# User_Interface.net
KiCad netlist of a schematic drawn in Altium Designer
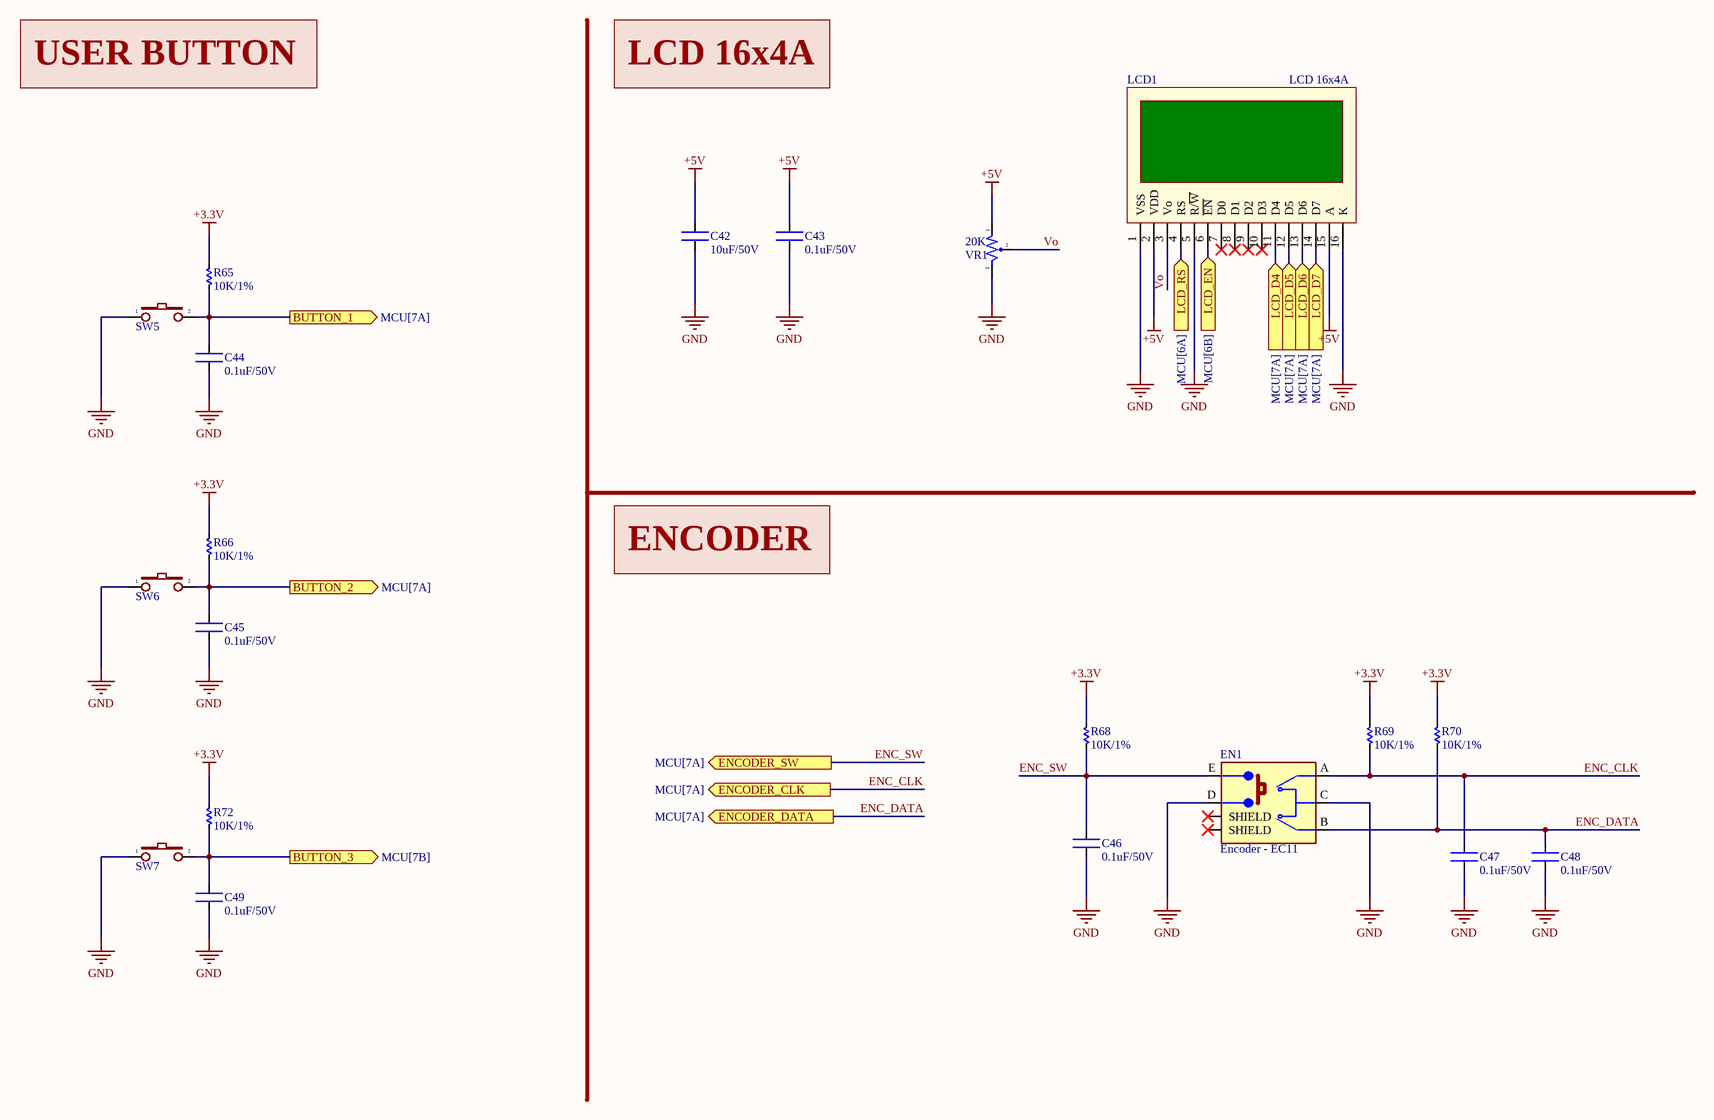
[diagram p0: User_Interface.SchDoc]

(export (version "E")
  (design (tool "Eeschema 10.0.6"))
  (components
    (comp (ref "C42")
      (value "10uF/50V")
      (footprint "CAP - 0603")
      (description "CAPACITOR SMD - KEMET")
      (libsource (lib "NewLibrary") (part "CAPACITOR"))
    )
    (comp (ref "C43")
      (value "0.1uF/50V")
      (footprint "CAP - 0603")
      (description "CAPACITOR SMD - KEMET")
      (libsource (lib "NewLibrary") (part "CAPACITOR"))
    )
    (comp (ref "C44")
      (value "0.1uF/50V")
      (footprint "CAP - 0603")
      (description "CAPACITOR SMD - KEMET")
      (libsource (lib "NewLibrary") (part "CAPACITOR"))
    )
    (comp (ref "C45")
      (value "0.1uF/50V")
      (footprint "CAP - 0603")
      (description "CAPACITOR SMD - KEMET")
      (libsource (lib "NewLibrary") (part "CAPACITOR"))
    )
    (comp (ref "C46")
      (value "0.1uF/50V")
      (footprint "CAP - 0603")
      (description "CAPACITOR SMD - KEMET")
      (libsource (lib "NewLibrary") (part "CAPACITOR"))
    )
    (comp (ref "C47")
      (value "0.1uF/50V")
      (footprint "CAP - 0603")
      (description "CAPACITOR SMD - KEMET")
      (libsource (lib "NewLibrary") (part "CAPACITOR"))
    )
    (comp (ref "C48")
      (value "0.1uF/50V")
      (footprint "CAP - 0603")
      (description "CAPACITOR SMD - KEMET")
      (libsource (lib "NewLibrary") (part "CAPACITOR"))
    )
    (comp (ref "C49")
      (value "0.1uF/50V")
      (footprint "CAP - 0603")
      (description "CAPACITOR SMD - KEMET")
      (libsource (lib "NewLibrary") (part "CAPACITOR"))
    )
    (comp (ref "EN1")
      (value "Encoder - EC11")
      (footprint "Encoder - EC11")
      (description "Bourns PEC11R-4015F-S0024")
      (libsource (lib "NewLibrary") (part "Encoder - EC11"))
    )
    (comp (ref "LCD1")
      (value "LCD 16x4A")
      (footprint "LCD-16x4A-2-Holes")
      (description "Character LCD, 16x4, LED backlight.")
      (libsource (lib "NewLibrary") (part "LCD 16x4A"))
    )
    (comp (ref "R65")
      (value "10K/1%")
      (footprint "RES - 0603")
      (description "Resistor SMD - YAGEO")
      (libsource (lib "NewLibrary") (part "RESISTOR"))
    )
    (comp (ref "R66")
      (value "10K/1%")
      (footprint "RES - 0603")
      (description "Resistor SMD - YAGEO")
      (libsource (lib "NewLibrary") (part "RESISTOR"))
    )
    (comp (ref "R68")
      (value "10K/1%")
      (footprint "RES - 0603")
      (description "Resistor SMD - YAGEO")
      (libsource (lib "NewLibrary") (part "RESISTOR"))
    )
    (comp (ref "R69")
      (value "10K/1%")
      (footprint "RES - 0603")
      (description "Resistor SMD - YAGEO")
      (libsource (lib "NewLibrary") (part "RESISTOR"))
    )
    (comp (ref "R70")
      (value "10K/1%")
      (footprint "RES - 0603")
      (description "Resistor SMD - YAGEO")
      (libsource (lib "NewLibrary") (part "RESISTOR"))
    )
    (comp (ref "R72")
      (value "10K/1%")
      (footprint "RES - 0603")
      (description "Resistor SMD - YAGEO")
      (libsource (lib "NewLibrary") (part "RESISTOR"))
    )
    (comp (ref "SW5")
      (value "Button 4 Pins")
      (footprint "SW-SMD-6x6mm")
      (description "DIP Button 4 Pins")
      (libsource (lib "NewLibrary") (part "Button 4 Pins"))
    )
    (comp (ref "SW6")
      (value "Button 4 Pins")
      (footprint "SW-SMD-6x6mm")
      (description "DIP Button 4 Pins")
      (libsource (lib "NewLibrary") (part "Button 4 Pins"))
    )
    (comp (ref "SW7")
      (value "Button 4 Pins")
      (footprint "SW-SMD-6x6mm")
      (description "DIP Button 4 Pins")
      (libsource (lib "NewLibrary") (part "Button 4 Pins"))
    )
    (comp (ref "VR1")
      (value "20K")
      (footprint "VR 3x3")
      (description "VR")
      (libsource (lib "NewLibrary") (part "VARIABLE RESISTOR"))
    )
  )
  (nets
    (net (code "1") (name "+3.3V") (class "Default")
      (node (ref "R65") (pin "2") (pinfunction "2_2") (pintype "passive"))
      (node (ref "R66") (pin "2") (pinfunction "2_2") (pintype "passive"))
      (node (ref "R68") (pin "2") (pinfunction "2_2") (pintype "passive"))
      (node (ref "R69") (pin "2") (pinfunction "2_2") (pintype "passive"))
      (node (ref "R70") (pin "2") (pinfunction "2_2") (pintype "passive"))
      (node (ref "R72") (pin "1") (pinfunction "1_1") (pintype "passive"))
    )
    (net (code "2") (name "+5V") (class "Default")
      (node (ref "C42") (pin "2") (pinfunction "2_2") (pintype "passive"))
      (node (ref "C43") (pin "2") (pinfunction "2_2") (pintype "passive"))
      (node (ref "LCD1") (pin "15") (pinfunction "A_15") (pintype "passive"))
      (node (ref "LCD1") (pin "2") (pinfunction "VDD_2") (pintype "passive"))
      (node (ref "VR1") (pin "1") (pinfunction "1_1") (pintype "passive"))
    )
    (net (code "3") (name "/BUTTON_1") (class "Default")
      (node (ref "C44") (pin "2") (pinfunction "2_2") (pintype "passive"))
      (node (ref "R65") (pin "1") (pinfunction "1_1") (pintype "passive"))
      (node (ref "SW5") (pin "2") (pinfunction "2_2") (pintype "passive"))
    )
    (net (code "4") (name "/BUTTON_2") (class "Default")
      (node (ref "C45") (pin "2") (pinfunction "2_2") (pintype "passive"))
      (node (ref "R66") (pin "1") (pinfunction "1_1") (pintype "passive"))
      (node (ref "SW6") (pin "2") (pinfunction "2_2") (pintype "passive"))
    )
    (net (code "5") (name "/BUTTON_3") (class "Default")
      (node (ref "C49") (pin "2") (pinfunction "2_2") (pintype "passive"))
      (node (ref "R72") (pin "2") (pinfunction "2_2") (pintype "passive"))
      (node (ref "SW7") (pin "2") (pinfunction "2_2") (pintype "passive"))
    )
    (net (code "6") (name "/ENC_CLK") (class "Default")
      (node (ref "C47") (pin "2") (pinfunction "2_2") (pintype "passive"))
      (node (ref "EN1") (pin "A") (pinfunction "A_A") (pintype "passive"))
      (node (ref "R69") (pin "1") (pinfunction "1_1") (pintype "passive"))
    )
    (net (code "7") (name "/ENC_DATA") (class "Default")
      (node (ref "C48") (pin "2") (pinfunction "2_2") (pintype "passive"))
      (node (ref "EN1") (pin "B") (pinfunction "B_B") (pintype "passive"))
      (node (ref "R70") (pin "1") (pinfunction "1_1") (pintype "passive"))
    )
    (net (code "8") (name "/ENC_SW") (class "Default")
      (node (ref "C46") (pin "2") (pinfunction "2_2") (pintype "passive"))
      (node (ref "EN1") (pin "E") (pinfunction "S2_E") (pintype "passive"))
      (node (ref "R68") (pin "1") (pinfunction "1_1") (pintype "passive"))
    )
    (net (code "9") (name "/LCD_D4") (class "Default")
      (node (ref "LCD1") (pin "11") (pinfunction "D4_11") (pintype "passive"))
    )
    (net (code "10") (name "/LCD_D5") (class "Default")
      (node (ref "LCD1") (pin "12") (pinfunction "D5_12") (pintype "passive"))
    )
    (net (code "11") (name "/LCD_D6") (class "Default")
      (node (ref "LCD1") (pin "13") (pinfunction "D6_13") (pintype "passive"))
    )
    (net (code "12") (name "/LCD_D7") (class "Default")
      (node (ref "LCD1") (pin "14") (pinfunction "D7_14") (pintype "passive"))
    )
    (net (code "13") (name "/LCD_EN") (class "Default")
      (node (ref "LCD1") (pin "6") (pinfunction "~{EN}_6") (pintype "passive"))
    )
    (net (code "14") (name "/LCD_RS") (class "Default")
      (node (ref "LCD1") (pin "4") (pinfunction "RS_4") (pintype "passive"))
    )
    (net (code "15") (name "/Vo") (class "Default")
      (node (ref "LCD1") (pin "3") (pinfunction "Vo_3") (pintype "passive"))
      (node (ref "VR1") (pin "2") (pinfunction "2_2") (pintype "passive"))
    )
    (net (code "16") (name "GND") (class "Default")
      (node (ref "C42") (pin "1") (pinfunction "1_1") (pintype "passive"))
      (node (ref "C43") (pin "1") (pinfunction "1_1") (pintype "passive"))
      (node (ref "C44") (pin "1") (pinfunction "1_1") (pintype "passive"))
      (node (ref "C45") (pin "1") (pinfunction "1_1") (pintype "passive"))
      (node (ref "C46") (pin "1") (pinfunction "1_1") (pintype "passive"))
      (node (ref "C47") (pin "1") (pinfunction "1_1") (pintype "passive"))
      (node (ref "C48") (pin "1") (pinfunction "1_1") (pintype "passive"))
      (node (ref "C49") (pin "1") (pinfunction "1_1") (pintype "passive"))
      (node (ref "EN1") (pin "C") (pinfunction "C_C") (pintype "passive"))
      (node (ref "EN1") (pin "D") (pinfunction "S1_D") (pintype "passive"))
      (node (ref "LCD1") (pin "1") (pinfunction "VSS_1") (pintype "passive"))
      (node (ref "LCD1") (pin "16") (pinfunction "K_16") (pintype "passive"))
      (node (ref "LCD1") (pin "5") (pinfunction "R/~{W}_5") (pintype "passive"))
      (node (ref "SW5") (pin "1") (pinfunction "1_1") (pintype "passive"))
      (node (ref "SW6") (pin "1") (pinfunction "1_1") (pintype "passive"))
      (node (ref "SW7") (pin "1") (pinfunction "1_1") (pintype "passive"))
      (node (ref "VR1") (pin "3") (pinfunction "3_3") (pintype "passive"))
    )
    (net (code "17") (name "unconnected-(EN1-SHIELD-PadSH1)") (class "Default")
      (node (ref "EN1") (pin "SH1") (pinfunction "SHIELD_SH1") (pintype "passive+no_connect"))
    )
    (net (code "18") (name "unconnected-(EN1-SHIELD-PadSH2)") (class "Default")
      (node (ref "EN1") (pin "SH2") (pinfunction "SHIELD_SH2") (pintype "passive+no_connect"))
    )
    (net (code "19") (name "unconnected-(LCD1-D0-Pad7)") (class "Default")
      (node (ref "LCD1") (pin "7") (pinfunction "D0_7") (pintype "passive+no_connect"))
    )
    (net (code "20") (name "unconnected-(LCD1-D1-Pad8)") (class "Default")
      (node (ref "LCD1") (pin "8") (pinfunction "D1_8") (pintype "passive+no_connect"))
    )
    (net (code "21") (name "unconnected-(LCD1-D2-Pad9)") (class "Default")
      (node (ref "LCD1") (pin "9") (pinfunction "D2_9") (pintype "passive+no_connect"))
    )
    (net (code "22") (name "unconnected-(LCD1-D3-Pad10)") (class "Default")
      (node (ref "LCD1") (pin "10") (pinfunction "D3_10") (pintype "passive+no_connect"))
    )
  )
)
